# MFP_PCB.net
KiCad netlist of a schematic drawn in EAGLE
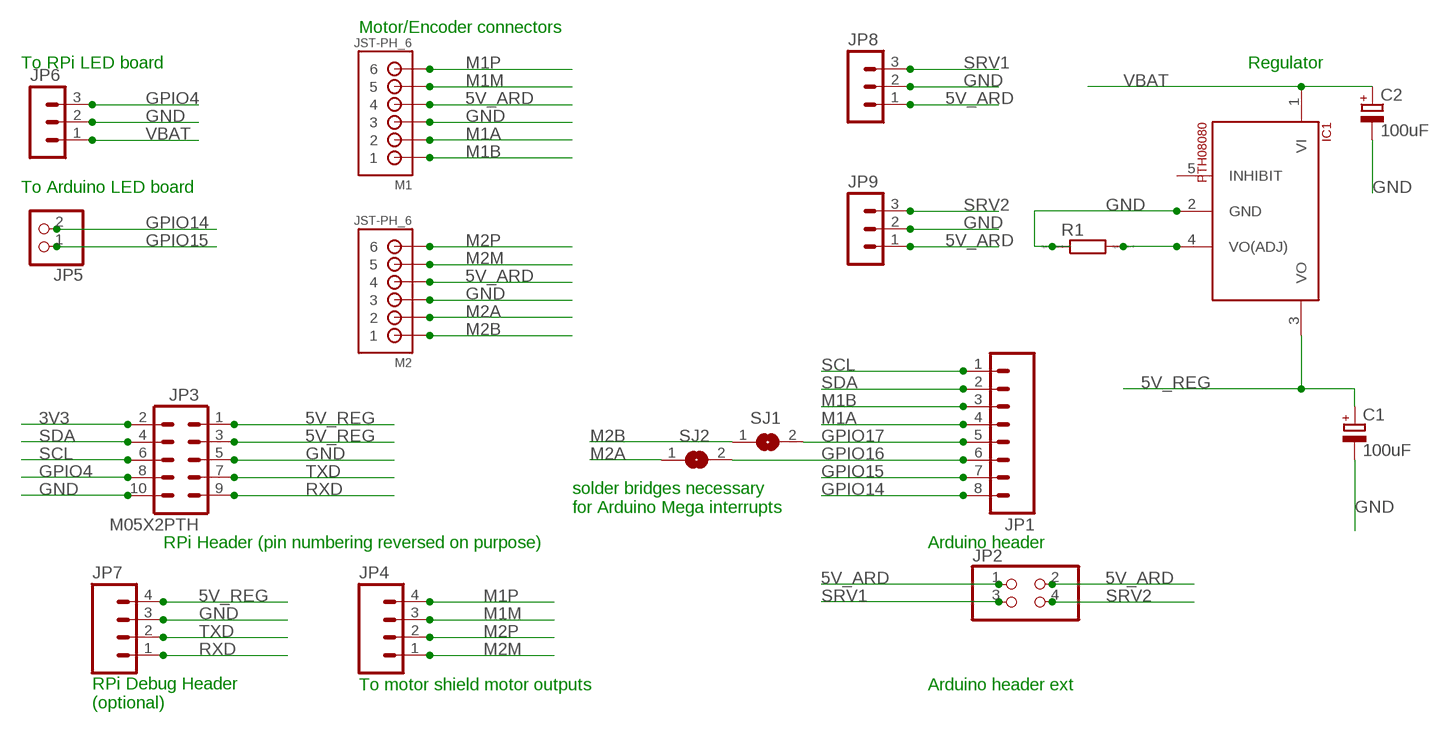
[diagram p0: schematic, sheet 1]

(export (version "E")
  (design (tool "Eeschema 10.0.6"))
  (components
    (comp (ref "C1")
      (value "100uF")
      (footprint "eagle-import:150CLZ-0810")
      (libsource (lib "eagle-import") (part "CPOL-EU150CLZ-0810"))
    )
    (comp (ref "C2")
      (value "100uF")
      (footprint "eagle-import:150CLZ-0810")
      (libsource (lib "eagle-import") (part "CPOL-EU150CLZ-0810"))
    )
    (comp (ref "IC1")
      (value "PTH08080")
      (footprint "eagle-import:PTH08080")
      (libsource (lib "eagle-import") (part "PTH08080"))
    )
    (comp (ref "JP1")
      (value "M08LONGPADS")
      (footprint "eagle-import:1X08_LONGPADS")
      (libsource (lib "eagle-import") (part "M08LONGPADS"))
    )
    (comp (ref "JP2")
      (value "PINHD-2X2")
      (footprint "eagle-import:2X02")
      (libsource (lib "eagle-import") (part "PINHD-2X2"))
    )
    (comp (ref "JP3")
      (value "M05X2PTH")
      (footprint "eagle-import:AVR_ICSP")
      (libsource (lib "eagle-import") (part "M05X2PTH"))
    )
    (comp (ref "JP4")
      (value "M04PTH")
      (footprint "eagle-import:1X04")
      (libsource (lib "eagle-import") (part "M04PTH"))
    )
    (comp (ref "JP5")
      (value "PINHD-1X2")
      (footprint "eagle-import:1X02")
      (libsource (lib "eagle-import") (part "PINHD-1X2"))
    )
    (comp (ref "JP6")
      (value "MA03-1")
      (footprint "eagle-import:MA03-1")
      (libsource (lib "eagle-import") (part "MA03-1"))
    )
    (comp (ref "JP7")
      (value "M04PTH")
      (footprint "eagle-import:1X04")
      (libsource (lib "eagle-import") (part "M04PTH"))
    )
    (comp (ref "JP8")
      (value "MA03-1")
      (footprint "eagle-import:MA03-1")
      (libsource (lib "eagle-import") (part "MA03-1"))
    )
    (comp (ref "JP9")
      (value "MA03-1")
      (footprint "eagle-import:MA03-1")
      (libsource (lib "eagle-import") (part "MA03-1"))
    )
    (comp (ref "M1")
      (value "JST-PH_6")
      (footprint "eagle-import:JST_B6B-PH_HEADER")
      (libsource (lib "eagle-import") (part "JST-PH_6"))
    )
    (comp (ref "M2")
      (value "JST-PH_6")
      (footprint "eagle-import:JST_B6B-PH_HEADER")
      (libsource (lib "eagle-import") (part "JST-PH_6"))
    )
    (comp (ref "R1")
      (value "R0204/7")
      (footprint "eagle-import:0204_7")
      (libsource (lib "eagle-import") (part "R0204/7"))
    )
    (comp (ref "SJ1") (value "SJ") (footprint "eagle-import:SJ") (libsource (lib "eagle-import") (part "SJ")))
    (comp (ref "SJ2") (value "SJ") (footprint "eagle-import:SJ") (libsource (lib "eagle-import") (part "SJ")))
  )
  (nets
    (net (code "1") (name "/3V3") (class "Default")
      (node (ref "JP3") (pin "2") (pinfunction "2_2") (pintype "passive"))
    )
    (net (code "2") (name "/5V_ARD") (class "Default")
      (node (ref "JP2") (pin "1") (pinfunction "1_1") (pintype "passive"))
      (node (ref "JP2") (pin "2") (pinfunction "2_2") (pintype "passive"))
      (node (ref "JP8") (pin "1") (pinfunction "1_1") (pintype "passive"))
      (node (ref "JP9") (pin "1") (pinfunction "1_1") (pintype "passive"))
      (node (ref "M1") (pin "P4") (pinfunction "4_P4") (pintype "bidirectional"))
      (node (ref "M2") (pin "P4") (pinfunction "4_P4") (pintype "bidirectional"))
    )
    (net (code "3") (name "/5V_REG") (class "Default")
      (node (ref "C1") (pin "+") (pinfunction "+_+") (pintype "passive"))
      (node (ref "IC1") (pin "3") (pinfunction "VO_3") (pintype "bidirectional"))
      (node (ref "JP3") (pin "1") (pinfunction "1_1") (pintype "passive"))
      (node (ref "JP3") (pin "3") (pinfunction "3_3") (pintype "passive"))
      (node (ref "JP7") (pin "4") (pinfunction "4_4") (pintype "passive"))
    )
    (net (code "4") (name "/GND") (class "Default")
      (node (ref "C1") (pin "-") (pinfunction "-_-") (pintype "passive"))
      (node (ref "C2") (pin "-") (pinfunction "-_-") (pintype "passive"))
      (node (ref "IC1") (pin "2") (pinfunction "GND_2") (pintype "bidirectional"))
      (node (ref "JP3") (pin "10") (pinfunction "10_10") (pintype "passive"))
      (node (ref "JP3") (pin "5") (pinfunction "5_5") (pintype "passive"))
      (node (ref "JP6") (pin "2") (pinfunction "2_2") (pintype "passive"))
      (node (ref "JP7") (pin "3") (pinfunction "3_3") (pintype "passive"))
      (node (ref "JP8") (pin "2") (pinfunction "2_2") (pintype "passive"))
      (node (ref "JP9") (pin "2") (pinfunction "2_2") (pintype "passive"))
      (node (ref "M1") (pin "P3") (pinfunction "3_P3") (pintype "bidirectional"))
      (node (ref "M2") (pin "P3") (pinfunction "3_P3") (pintype "bidirectional"))
      (node (ref "R1") (pin "1") (pinfunction "1_1") (pintype "passive"))
    )
    (net (code "5") (name "/GPIO4") (class "Default")
      (node (ref "JP3") (pin "8") (pinfunction "8_8") (pintype "passive"))
      (node (ref "JP6") (pin "3") (pinfunction "3_3") (pintype "passive"))
    )
    (net (code "6") (name "/GPIO14") (class "Default")
      (node (ref "JP1") (pin "8") (pinfunction "8_8") (pintype "passive"))
      (node (ref "JP5") (pin "2") (pinfunction "2_2") (pintype "passive"))
    )
    (net (code "7") (name "/GPIO15") (class "Default")
      (node (ref "JP1") (pin "7") (pinfunction "7_7") (pintype "passive"))
      (node (ref "JP5") (pin "1") (pinfunction "1_1") (pintype "passive"))
    )
    (net (code "8") (name "/GPIO16") (class "Default")
      (node (ref "JP1") (pin "6") (pinfunction "6_6") (pintype "passive"))
      (node (ref "SJ2") (pin "2") (pinfunction "2_2") (pintype "passive"))
    )
    (net (code "9") (name "/GPIO17") (class "Default")
      (node (ref "JP1") (pin "5") (pinfunction "5_5") (pintype "passive"))
      (node (ref "SJ1") (pin "2") (pinfunction "2_2") (pintype "passive"))
    )
    (net (code "10") (name "/M1A") (class "Default")
      (node (ref "JP1") (pin "4") (pinfunction "4_4") (pintype "passive"))
      (node (ref "M1") (pin "P2") (pinfunction "2_P2") (pintype "bidirectional"))
    )
    (net (code "11") (name "/M1B") (class "Default")
      (node (ref "JP1") (pin "3") (pinfunction "3_3") (pintype "passive"))
      (node (ref "M1") (pin "P1") (pinfunction "1_P1") (pintype "bidirectional"))
    )
    (net (code "12") (name "/M1M") (class "Default")
      (node (ref "JP4") (pin "3") (pinfunction "3_3") (pintype "passive"))
      (node (ref "M1") (pin "P5") (pinfunction "5_P5") (pintype "bidirectional"))
    )
    (net (code "13") (name "/M1P") (class "Default")
      (node (ref "JP4") (pin "4") (pinfunction "4_4") (pintype "passive"))
      (node (ref "M1") (pin "P6") (pinfunction "6_P6") (pintype "bidirectional"))
    )
    (net (code "14") (name "/M2A") (class "Default")
      (node (ref "M2") (pin "P2") (pinfunction "2_P2") (pintype "bidirectional"))
      (node (ref "SJ2") (pin "1") (pinfunction "1_1") (pintype "passive"))
    )
    (net (code "15") (name "/M2B") (class "Default")
      (node (ref "M2") (pin "P1") (pinfunction "1_P1") (pintype "bidirectional"))
      (node (ref "SJ1") (pin "1") (pinfunction "1_1") (pintype "passive"))
    )
    (net (code "16") (name "/M2M") (class "Default")
      (node (ref "JP4") (pin "1") (pinfunction "1_1") (pintype "passive"))
      (node (ref "M2") (pin "P5") (pinfunction "5_P5") (pintype "bidirectional"))
    )
    (net (code "17") (name "/M2P") (class "Default")
      (node (ref "JP4") (pin "2") (pinfunction "2_2") (pintype "passive"))
      (node (ref "M2") (pin "P6") (pinfunction "6_P6") (pintype "bidirectional"))
    )
    (net (code "18") (name "/RXD") (class "Default")
      (node (ref "JP3") (pin "9") (pinfunction "9_9") (pintype "passive"))
      (node (ref "JP7") (pin "1") (pinfunction "1_1") (pintype "passive"))
    )
    (net (code "19") (name "/SCL") (class "Default")
      (node (ref "JP1") (pin "1") (pinfunction "1_1") (pintype "passive"))
      (node (ref "JP3") (pin "6") (pinfunction "6_6") (pintype "passive"))
    )
    (net (code "20") (name "/SDA") (class "Default")
      (node (ref "JP1") (pin "2") (pinfunction "2_2") (pintype "passive"))
      (node (ref "JP3") (pin "4") (pinfunction "4_4") (pintype "passive"))
    )
    (net (code "21") (name "/SRV1") (class "Default")
      (node (ref "JP2") (pin "3") (pinfunction "3_3") (pintype "passive"))
      (node (ref "JP8") (pin "3") (pinfunction "3_3") (pintype "passive"))
    )
    (net (code "22") (name "/SRV2") (class "Default")
      (node (ref "JP2") (pin "4") (pinfunction "4_4") (pintype "passive"))
      (node (ref "JP9") (pin "3") (pinfunction "3_3") (pintype "passive"))
    )
    (net (code "23") (name "/TXD") (class "Default")
      (node (ref "JP3") (pin "7") (pinfunction "7_7") (pintype "passive"))
      (node (ref "JP7") (pin "2") (pinfunction "2_2") (pintype "passive"))
    )
    (net (code "24") (name "/VBAT") (class "Default")
      (node (ref "C2") (pin "+") (pinfunction "+_+") (pintype "passive"))
      (node (ref "IC1") (pin "1") (pinfunction "VI_1") (pintype "bidirectional"))
      (node (ref "JP6") (pin "1") (pinfunction "1_1") (pintype "passive"))
    )
    (net (code "25") (name "Net-(IC1-VO(ADJ))") (class "Default")
      (node (ref "IC1") (pin "4") (pinfunction "VO(ADJ)_4") (pintype "bidirectional"))
      (node (ref "R1") (pin "2") (pinfunction "2_2") (pintype "passive"))
    )
    (net (code "26") (name "unconnected-(IC1-INHIBIT-Pad5)") (class "Default")
      (node (ref "IC1") (pin "5") (pinfunction "INHIBIT_5") (pintype "bidirectional"))
    )
  )
)
